# ljus_sch.net
KiCad netlist of a schematic drawn in Altium Designer
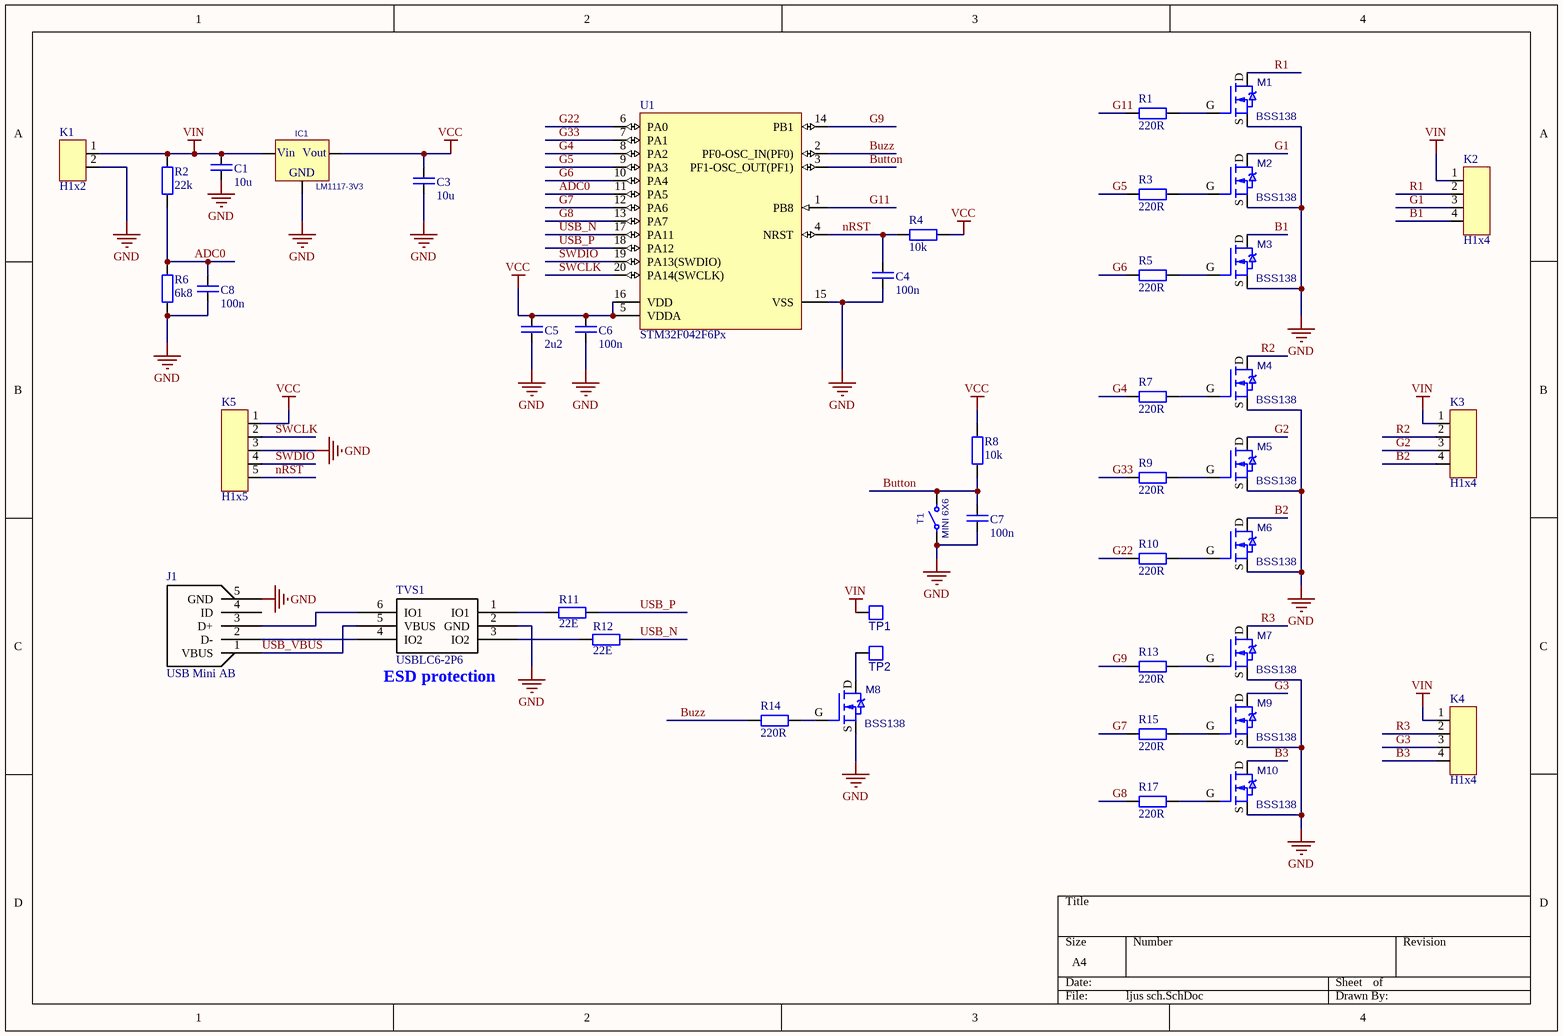
[diagram p0: ljus sch.SchDoc]

(export (version "E")
  (design (tool "Eeschema 10.0.6"))
  (components
    (comp (ref "C1")
      (value "10u")
      (footprint "C0805(2012)_M")
      (description "Capacitor")
      (libsource (lib "General") (part "C"))
    )
    (comp (ref "C3")
      (value "10u")
      (footprint "C0805(2012)_M")
      (description "Capacitor")
      (libsource (lib "General") (part "C"))
    )
    (comp (ref "C4")
      (value "100n")
      (footprint "0603")
      (description "Capacitor")
      (libsource (lib "General") (part "C"))
    )
    (comp (ref "C5")
      (value "2u2")
      (footprint "0603")
      (description "Capacitor")
      (libsource (lib "General") (part "C"))
    )
    (comp (ref "C6")
      (value "100n")
      (footprint "0603")
      (description "Capacitor")
      (libsource (lib "General") (part "C"))
    )
    (comp (ref "C7")
      (value "100n")
      (footprint "0603")
      (description "Capacitor")
      (libsource (lib "General") (part "C"))
    )
    (comp (ref "C8")
      (value "100n")
      (footprint "0603")
      (description "Capacitor")
      (libsource (lib "General") (part "C"))
    )
    (comp (ref "IC1")
      (value "LM1117-3V3")
      (footprint "SOT233")
      (libsource (lib "ICgeneral") (part "LM1117-3V3"))
    )
    (comp (ref "J1")
      (value "USB Mini AB")
      (footprint "USB3131-30-0230-A")
      (description "SOCKET, USB MINI-AB THRU HOLE")
      (fields (field (name "MANUFACTURER") "MOLEX") (field (name "PART NUMBER") "565790511"))
      (libsource (lib "moja") (part "USB Mini AB"))
    )
    (comp (ref "K1")
      (value "H1x2")
      (footprint "XT-30")
      (description "Header 1x2 (male)")
      (libsource (lib "Kon_Tipk") (part "H1x2"))
    )
    (comp (ref "K2")
      (value "H1x4")
      (footprint "H1x4")
      (description "Header 1x4 (male)")
      (libsource (lib "Kon_Tipk") (part "H1x4"))
    )
    (comp (ref "K3")
      (value "H1x4")
      (footprint "H1x4")
      (description "Header 1x4 (male)")
      (libsource (lib "Kon_Tipk") (part "H1x4"))
    )
    (comp (ref "K4")
      (value "H1x4")
      (footprint "H1x4")
      (description "Header 1x4 (male)")
      (libsource (lib "Kon_Tipk") (part "H1x4"))
    )
    (comp (ref "K5")
      (value "H1x5")
      (footprint "H1x5")
      (description "Header 1x5 (male)")
      (libsource (lib "Kon_Tipk") (part "H1x5"))
    )
    (comp (ref "M1") (value "BSS138") (footprint "SOT23-BSS138") (libsource (lib "SemiCond") (part "BSS138")))
    (comp (ref "M2") (value "BSS138") (footprint "SOT23-BSS138") (libsource (lib "SemiCond") (part "BSS138")))
    (comp (ref "M3") (value "BSS138") (footprint "SOT23-BSS138") (libsource (lib "SemiCond") (part "BSS138")))
    (comp (ref "M4") (value "BSS138") (footprint "SOT23-BSS138") (libsource (lib "SemiCond") (part "BSS138")))
    (comp (ref "M5") (value "BSS138") (footprint "SOT23-BSS138") (libsource (lib "SemiCond") (part "BSS138")))
    (comp (ref "M6") (value "BSS138") (footprint "SOT23-BSS138") (libsource (lib "SemiCond") (part "BSS138")))
    (comp (ref "M7") (value "BSS138") (footprint "SOT23-BSS138") (libsource (lib "SemiCond") (part "BSS138")))
    (comp (ref "M8") (value "BSS138") (footprint "SOT23-BSS138") (libsource (lib "SemiCond") (part "BSS138")))
    (comp (ref "M9") (value "BSS138") (footprint "SOT23-BSS138") (libsource (lib "SemiCond") (part "BSS138")))
    (comp (ref "M10")
      (value "BSS138")
      (footprint "SOT23-BSS138")
      (libsource (lib "SemiCond") (part "BSS138"))
    )
    (comp (ref "R1") (value "220R") (footprint "0603") (description "R") (libsource (lib "moje") (part "R")))
    (comp (ref "R2")
      (value "22k")
      (footprint "0603")
      (description "R")
      (libsource (lib "General") (part "R"))
    )
    (comp (ref "R3") (value "220R") (footprint "0603") (description "R") (libsource (lib "moje") (part "R")))
    (comp (ref "R4")
      (value "10k")
      (footprint "0603")
      (description "R")
      (libsource (lib "General") (part "R"))
    )
    (comp (ref "R5") (value "220R") (footprint "0603") (description "R") (libsource (lib "moje") (part "R")))
    (comp (ref "R6")
      (value "6k8")
      (footprint "0603")
      (description "R")
      (libsource (lib "General") (part "R"))
    )
    (comp (ref "R7") (value "220R") (footprint "0603") (description "R") (libsource (lib "moje") (part "R")))
    (comp (ref "R8")
      (value "10k")
      (footprint "0603")
      (description "R")
      (libsource (lib "General") (part "R"))
    )
    (comp (ref "R9") (value "220R") (footprint "0603") (description "R") (libsource (lib "moje") (part "R")))
    (comp (ref "R10") (value "220R") (footprint "0603") (description "R") (libsource (lib "moje") (part "R")))
    (comp (ref "R11")
      (value "22E")
      (footprint "0603")
      (description "Resistor")
      (fields (field (name "PUBLISHER") "Altium Limited"))
      (libsource (lib "Miscellaneous Devices") (part "Res2"))
    )
    (comp (ref "R12")
      (value "22E")
      (footprint "0603")
      (description "Resistor")
      (fields (field (name "PUBLISHER") "Altium Limited"))
      (libsource (lib "Miscellaneous Devices") (part "Res2"))
    )
    (comp (ref "R13") (value "220R") (footprint "0603") (description "R") (libsource (lib "moje") (part "R")))
    (comp (ref "R14")
      (value "220R")
      (footprint "0603")
      (description "R")
      (libsource (lib "General") (part "R"))
    )
    (comp (ref "R15") (value "220R") (footprint "0603") (description "R") (libsource (lib "moje") (part "R")))
    (comp (ref "R17") (value "220R") (footprint "0603") (description "R") (libsource (lib "moje") (part "R")))
    (comp (ref "T1")
      (value "MINI 6X6")
      (footprint "SW 5x6 SMD SHORT")
      (libsource (lib "Kon_Tipk") (part "MINI 6X6"))
    )
    (comp (ref "TP1") (value "PAD") (footprint "PAD_CIRC_HOLE") (libsource (lib "General") (part "PAD")))
    (comp (ref "TP2") (value "PAD") (footprint "PAD_CIRC_HOLE") (libsource (lib "General") (part "PAD")))
    (comp (ref "TVS1")
      (value "USBLC6-2P6")
      (footprint "SOT23127P600-8N")
      (libsource (lib "moja") (part "USBLC6-2P6"))
    )
    (comp (ref "U1")
      (value "STM32F042F6Px")
      (footprint "STM-TSSOP20_M")
      (libsource (lib "STMicroelectronics STM32 F0") (part "STM32F042F6Px"))
    )
  )
  (nets
    (net (code "1") (name "/ADC0") (class "Default")
      (node (ref "C8") (pin "1") (pinfunction "1_1") (pintype "passive"))
      (node (ref "R2") (pin "2") (pintype "passive"))
      (node (ref "R6") (pin "1") (pintype "passive"))
      (node (ref "U1") (pin "11") (pinfunction "PA5_11") (pintype "bidirectional"))
    )
    (net (code "2") (name "/B1") (class "Default")
      (node (ref "K2") (pin "4") (pinfunction "4_4") (pintype "passive"))
      (node (ref "M3") (pin "D") (pintype "passive"))
    )
    (net (code "3") (name "/B2") (class "Default")
      (node (ref "K3") (pin "4") (pinfunction "4_4") (pintype "passive"))
      (node (ref "M6") (pin "D") (pintype "passive"))
    )
    (net (code "4") (name "/B3") (class "Default")
      (node (ref "K4") (pin "4") (pinfunction "4_4") (pintype "passive"))
      (node (ref "M10") (pin "D") (pintype "passive"))
    )
    (net (code "5") (name "/Button") (class "Default")
      (node (ref "C7") (pin "1") (pinfunction "1_1") (pintype "passive"))
      (node (ref "R8") (pin "1") (pintype "passive"))
      (node (ref "T1") (pin "2") (pintype "passive"))
      (node (ref "U1") (pin "3") (pinfunction "PF1-OSC_OUT(PF1)_3") (pintype "bidirectional"))
    )
    (net (code "6") (name "/Buzz") (class "Default")
      (node (ref "R14") (pin "1") (pintype "passive"))
      (node (ref "U1") (pin "2") (pinfunction "PF0-OSC_IN(PF0)_2") (pintype "bidirectional"))
    )
    (net (code "7") (name "/G1") (class "Default")
      (node (ref "K2") (pin "3") (pinfunction "3_3") (pintype "passive"))
      (node (ref "M2") (pin "D") (pintype "passive"))
    )
    (net (code "8") (name "/G2") (class "Default")
      (node (ref "K3") (pin "3") (pinfunction "3_3") (pintype "passive"))
      (node (ref "M5") (pin "D") (pintype "passive"))
    )
    (net (code "9") (name "/G3") (class "Default")
      (node (ref "K4") (pin "3") (pinfunction "3_3") (pintype "passive"))
      (node (ref "M9") (pin "D") (pintype "passive"))
    )
    (net (code "10") (name "/G4") (class "Default")
      (node (ref "R7") (pin "1") (pintype "passive"))
      (node (ref "U1") (pin "8") (pinfunction "PA2_8") (pintype "bidirectional"))
    )
    (net (code "11") (name "/G5") (class "Default")
      (node (ref "R3") (pin "1") (pintype "passive"))
      (node (ref "U1") (pin "9") (pinfunction "PA3_9") (pintype "bidirectional"))
    )
    (net (code "12") (name "/G6") (class "Default")
      (node (ref "R5") (pin "1") (pintype "passive"))
      (node (ref "U1") (pin "10") (pinfunction "PA4_10") (pintype "bidirectional"))
    )
    (net (code "13") (name "/G7") (class "Default")
      (node (ref "R15") (pin "1") (pintype "passive"))
      (node (ref "U1") (pin "12") (pinfunction "PA6_12") (pintype "bidirectional"))
    )
    (net (code "14") (name "/G8") (class "Default")
      (node (ref "R17") (pin "1") (pintype "passive"))
      (node (ref "U1") (pin "13") (pinfunction "PA7_13") (pintype "bidirectional"))
    )
    (net (code "15") (name "/G9") (class "Default")
      (node (ref "R13") (pin "1") (pintype "passive"))
      (node (ref "U1") (pin "14") (pinfunction "PB1_14") (pintype "bidirectional"))
    )
    (net (code "16") (name "/G11") (class "Default")
      (node (ref "R1") (pin "1") (pintype "passive"))
      (node (ref "U1") (pin "1") (pinfunction "PB8_1") (pintype "input"))
    )
    (net (code "17") (name "/G22") (class "Default")
      (node (ref "R10") (pin "1") (pintype "passive"))
      (node (ref "U1") (pin "6") (pinfunction "PA0_6") (pintype "bidirectional"))
    )
    (net (code "18") (name "/G33") (class "Default")
      (node (ref "R9") (pin "1") (pintype "passive"))
      (node (ref "U1") (pin "7") (pinfunction "PA1_7") (pintype "bidirectional"))
    )
    (net (code "19") (name "/R1") (class "Default")
      (node (ref "K2") (pin "2") (pinfunction "2_2") (pintype "passive"))
      (node (ref "M1") (pin "D") (pintype "passive"))
    )
    (net (code "20") (name "/R2") (class "Default")
      (node (ref "K3") (pin "2") (pinfunction "2_2") (pintype "passive"))
      (node (ref "M4") (pin "D") (pintype "passive"))
    )
    (net (code "21") (name "/R3") (class "Default")
      (node (ref "K4") (pin "2") (pinfunction "2_2") (pintype "passive"))
      (node (ref "M7") (pin "D") (pintype "passive"))
    )
    (net (code "22") (name "/SWCLK") (class "Default")
      (node (ref "K5") (pin "2") (pinfunction "2_2") (pintype "passive"))
      (node (ref "U1") (pin "20") (pinfunction "PA14(SWCLK)_20") (pintype "bidirectional"))
    )
    (net (code "23") (name "/SWDIO") (class "Default")
      (node (ref "K5") (pin "4") (pinfunction "4_4") (pintype "passive"))
      (node (ref "U1") (pin "19") (pinfunction "PA13(SWDIO)_19") (pintype "bidirectional"))
    )
    (net (code "24") (name "/USB_N") (class "Default")
      (node (ref "R12") (pin "1") (pinfunction "1_1") (pintype "passive"))
      (node (ref "U1") (pin "17") (pinfunction "PA11_17") (pintype "bidirectional"))
    )
    (net (code "25") (name "/USB_P") (class "Default")
      (node (ref "R11") (pin "1") (pinfunction "1_1") (pintype "passive"))
      (node (ref "U1") (pin "18") (pinfunction "PA12_18") (pintype "bidirectional"))
    )
    (net (code "26") (name "/USB_VBUS") (class "Default")
      (node (ref "J1") (pin "1") (pinfunction "VBUS_1") (pintype "power_in"))
      (node (ref "TVS1") (pin "5") (pinfunction "VBUS_5") (pintype "passive"))
    )
    (net (code "27") (name "/nRST") (class "Default")
      (node (ref "C4") (pin "1") (pinfunction "1_1") (pintype "passive"))
      (node (ref "K5") (pin "5") (pinfunction "5_5") (pintype "passive"))
      (node (ref "R4") (pin "1") (pintype "passive"))
      (node (ref "U1") (pin "4") (pinfunction "NRST_4") (pintype "bidirectional"))
    )
    (net (code "28") (name "GND") (class "Default")
      (node (ref "C1") (pin "2") (pinfunction "2_2") (pintype "passive"))
      (node (ref "C3") (pin "2") (pinfunction "2_2") (pintype "passive"))
      (node (ref "C4") (pin "2") (pinfunction "2_2") (pintype "passive"))
      (node (ref "C5") (pin "2") (pinfunction "2_2") (pintype "passive"))
      (node (ref "C6") (pin "2") (pinfunction "2_2") (pintype "passive"))
      (node (ref "C7") (pin "2") (pinfunction "2_2") (pintype "passive"))
      (node (ref "C8") (pin "2") (pinfunction "2_2") (pintype "passive"))
      (node (ref "IC1") (pin "GND") (pinfunction "GND_GND") (pintype "passive"))
      (node (ref "J1") (pin "5") (pinfunction "GND_5") (pintype "power_in"))
      (node (ref "K1") (pin "2") (pinfunction "2_2") (pintype "passive"))
      (node (ref "K5") (pin "3") (pinfunction "3_3") (pintype "passive"))
      (node (ref "M1") (pin "S") (pintype "passive"))
      (node (ref "M10") (pin "S") (pintype "passive"))
      (node (ref "M2") (pin "S") (pintype "passive"))
      (node (ref "M3") (pin "S") (pintype "passive"))
      (node (ref "M4") (pin "S") (pintype "passive"))
      (node (ref "M5") (pin "S") (pintype "passive"))
      (node (ref "M6") (pin "S") (pintype "passive"))
      (node (ref "M7") (pin "S") (pintype "passive"))
      (node (ref "M8") (pin "S") (pintype "passive"))
      (node (ref "M9") (pin "S") (pintype "passive"))
      (node (ref "R6") (pin "2") (pintype "passive"))
      (node (ref "T1") (pin "1") (pintype "passive"))
      (node (ref "TVS1") (pin "2") (pinfunction "GND_2") (pintype "passive"))
      (node (ref "U1") (pin "15") (pinfunction "VSS_15") (pintype "power_in"))
    )
    (net (code "29") (name "Net-(J1-D+)") (class "Default")
      (node (ref "J1") (pin "3") (pinfunction "D+_3") (pintype "power_in"))
      (node (ref "TVS1") (pin "6") (pinfunction "IO1_6") (pintype "passive"))
    )
    (net (code "30") (name "Net-(J1-D-)") (class "Default")
      (node (ref "J1") (pin "2") (pinfunction "D-_2") (pintype "power_in"))
      (node (ref "TVS1") (pin "4") (pinfunction "IO2_4") (pintype "passive"))
    )
    (net (code "31") (name "Net-(M1-PadG)") (class "Default")
      (node (ref "M1") (pin "G") (pintype "passive"))
      (node (ref "R1") (pin "2") (pintype "passive"))
    )
    (net (code "32") (name "Net-(M2-PadG)") (class "Default")
      (node (ref "M2") (pin "G") (pintype "passive"))
      (node (ref "R3") (pin "2") (pintype "passive"))
    )
    (net (code "33") (name "Net-(M3-PadG)") (class "Default")
      (node (ref "M3") (pin "G") (pintype "passive"))
      (node (ref "R5") (pin "2") (pintype "passive"))
    )
    (net (code "34") (name "Net-(M4-PadG)") (class "Default")
      (node (ref "M4") (pin "G") (pintype "passive"))
      (node (ref "R7") (pin "2") (pintype "passive"))
    )
    (net (code "35") (name "Net-(M5-PadG)") (class "Default")
      (node (ref "M5") (pin "G") (pintype "passive"))
      (node (ref "R9") (pin "2") (pintype "passive"))
    )
    (net (code "36") (name "Net-(M6-PadG)") (class "Default")
      (node (ref "M6") (pin "G") (pintype "passive"))
      (node (ref "R10") (pin "2") (pintype "passive"))
    )
    (net (code "37") (name "Net-(M7-PadG)") (class "Default")
      (node (ref "M7") (pin "G") (pintype "passive"))
      (node (ref "R13") (pin "2") (pintype "passive"))
    )
    (net (code "38") (name "Net-(M8-PadD)") (class "Default")
      (node (ref "M8") (pin "D") (pintype "passive"))
      (node (ref "TP2") (pin "1") (pinfunction "1_1") (pintype "passive"))
    )
    (net (code "39") (name "Net-(M8-PadG)") (class "Default")
      (node (ref "M8") (pin "G") (pintype "passive"))
      (node (ref "R14") (pin "2") (pintype "passive"))
    )
    (net (code "40") (name "Net-(M9-PadG)") (class "Default")
      (node (ref "M9") (pin "G") (pintype "passive"))
      (node (ref "R15") (pin "2") (pintype "passive"))
    )
    (net (code "41") (name "Net-(M10-PadG)") (class "Default")
      (node (ref "M10") (pin "G") (pintype "passive"))
      (node (ref "R17") (pin "2") (pintype "passive"))
    )
    (net (code "42") (name "Net-(R11-Pad2)") (class "Default")
      (node (ref "R11") (pin "2") (pinfunction "2_2") (pintype "passive"))
      (node (ref "TVS1") (pin "1") (pinfunction "IO1_1") (pintype "passive"))
    )
    (net (code "43") (name "Net-(R12-Pad2)") (class "Default")
      (node (ref "R12") (pin "2") (pinfunction "2_2") (pintype "passive"))
      (node (ref "TVS1") (pin "3") (pinfunction "IO2_3") (pintype "passive"))
    )
    (net (code "44") (name "VCC") (class "Default")
      (node (ref "C3") (pin "1") (pinfunction "1_1") (pintype "passive"))
      (node (ref "C5") (pin "1") (pinfunction "1_1") (pintype "passive"))
      (node (ref "C6") (pin "1") (pinfunction "1_1") (pintype "passive"))
      (node (ref "IC1") (pin "OUT") (pinfunction "OUT_OUT") (pintype "passive"))
      (node (ref "K5") (pin "1") (pinfunction "1_1") (pintype "passive"))
      (node (ref "R4") (pin "2") (pintype "passive"))
      (node (ref "R8") (pin "2") (pintype "passive"))
      (node (ref "U1") (pin "16") (pinfunction "VDD_16") (pintype "power_in"))
      (node (ref "U1") (pin "5") (pinfunction "VDDA_5") (pintype "power_in"))
    )
    (net (code "45") (name "VIN") (class "Default")
      (node (ref "C1") (pin "1") (pinfunction "1_1") (pintype "passive"))
      (node (ref "IC1") (pin "IN") (pinfunction "IN_IN") (pintype "passive"))
      (node (ref "K1") (pin "1") (pinfunction "1_1") (pintype "passive"))
      (node (ref "K2") (pin "1") (pinfunction "1_1") (pintype "passive"))
      (node (ref "K3") (pin "1") (pinfunction "1_1") (pintype "passive"))
      (node (ref "K4") (pin "1") (pinfunction "1_1") (pintype "passive"))
      (node (ref "R2") (pin "1") (pintype "passive"))
      (node (ref "TP1") (pin "1") (pinfunction "1_1") (pintype "passive"))
    )
    (net (code "46") (name "unconnected-(J1-ID-Pad4)") (class "Default")
      (node (ref "J1") (pin "4") (pinfunction "ID_4") (pintype "power_in"))
    )
  )
)
